# UNIT_V3_LVDS_Board.net
KiCad netlist of a schematic drawn in Altium Designer
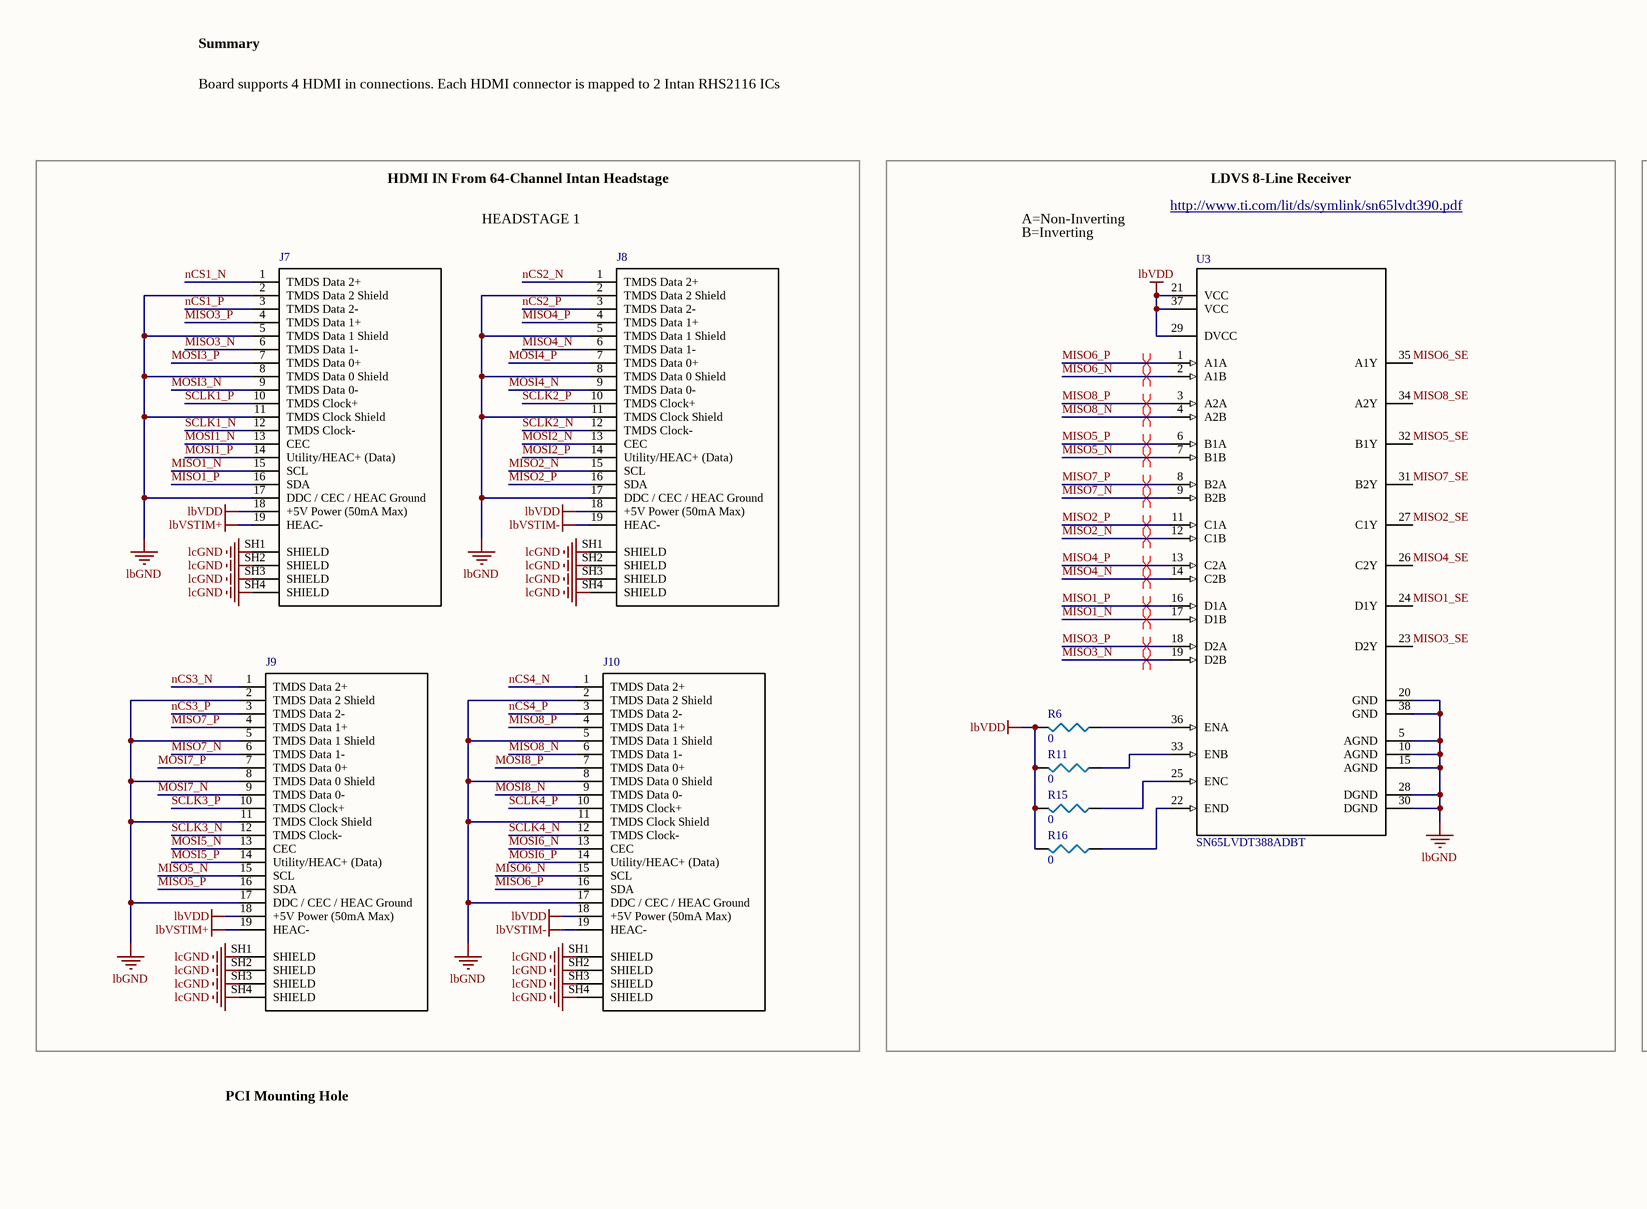
[diagram p0: UNIT_V3_LVDS_Board.SchDoc, left]
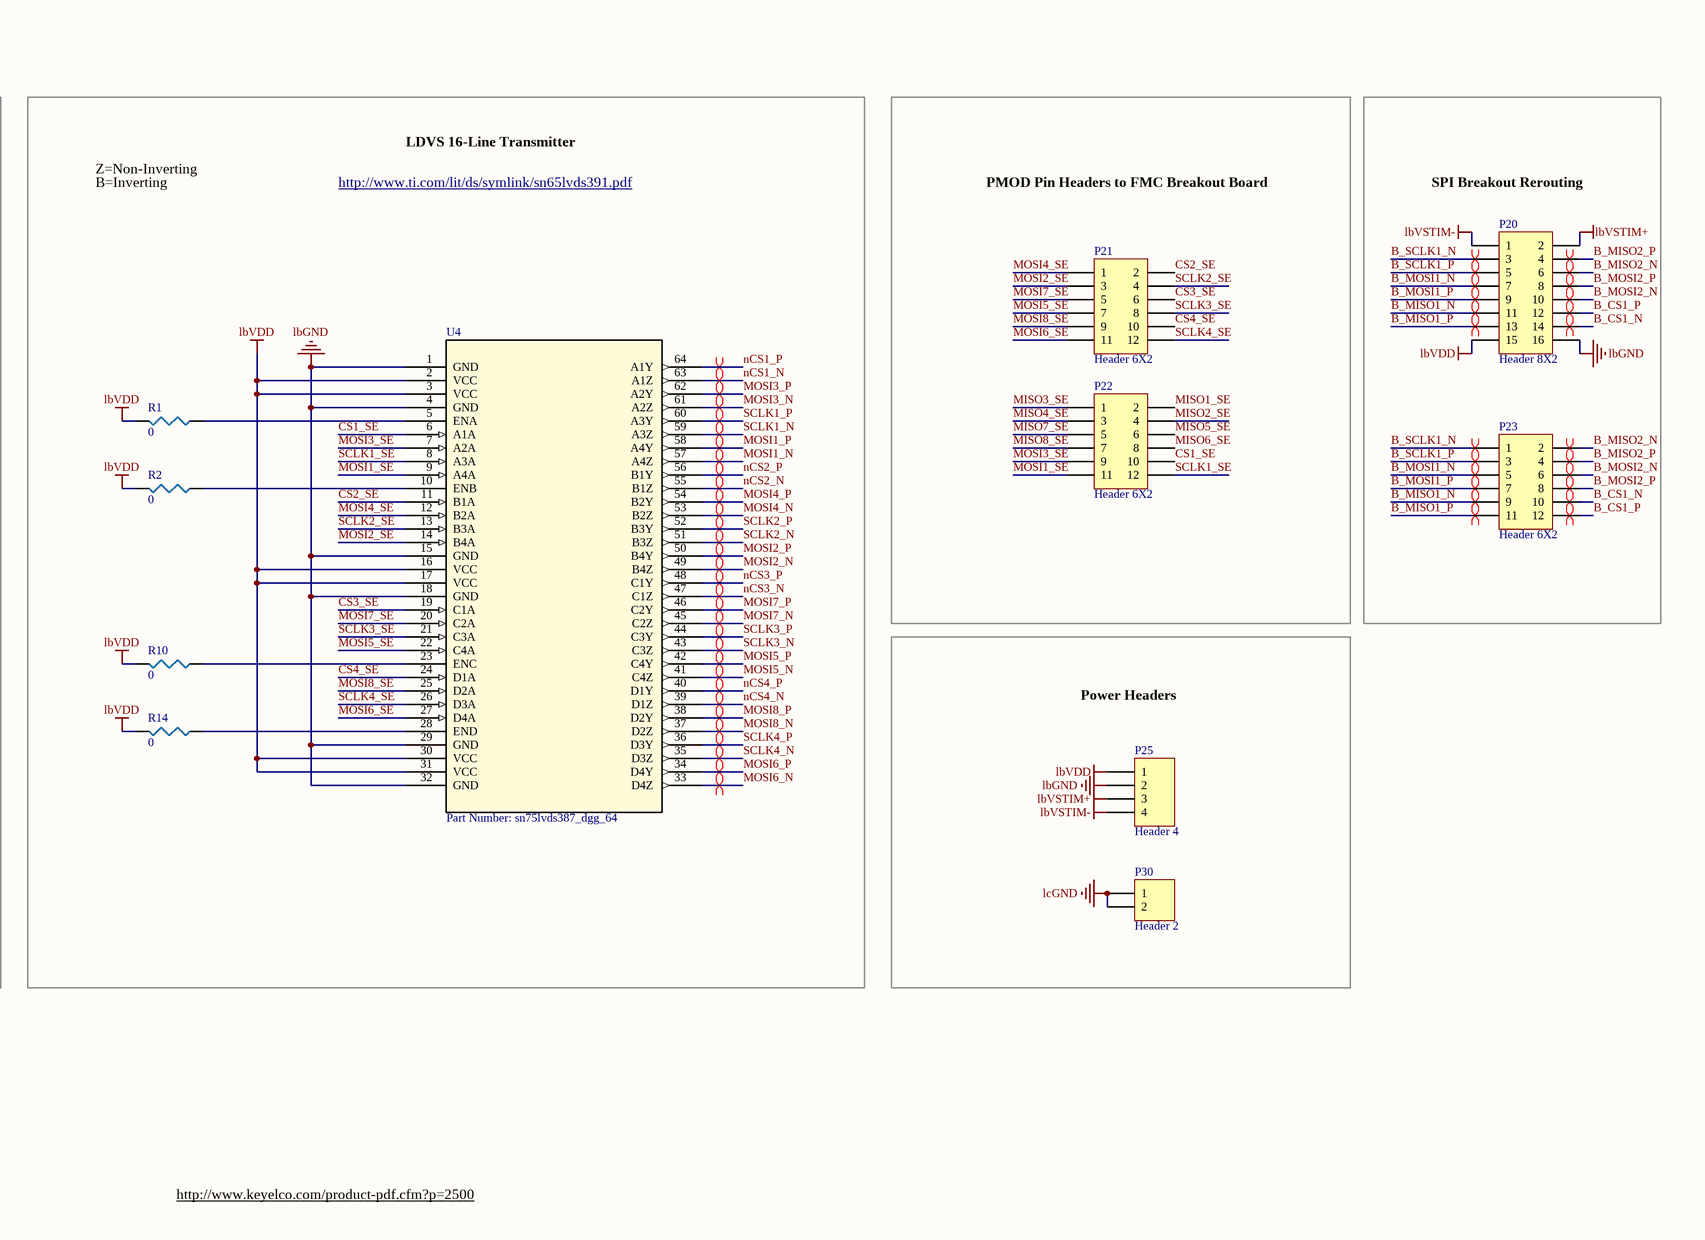
[diagram p1: UNIT_V3_LVDS_Board.SchDoc, right]

(export (version "E")
  (design (tool "Eeschema 10.0.6"))
  (components
    (comp (ref "J7")
      (value "1747981-2")
      (footprint "te_connectivity_audio_video_connectors:TE_1747981-2_1747981-2(Primary)")
      (description "Conn HDMI RCP 19 POS 0.5mm Solder ST SMD 19 Terminal 1 Port T/R")
      (fields (field (name "MF") "TE Connectivity"))
      (libsource (lib "te_connectivity_audio_video_connectors") (part "1747981-2"))
    )
    (comp (ref "J8")
      (value "1747981-2")
      (footprint "te_connectivity_audio_video_connectors:TE_1747981-2_1747981-2(Primary)")
      (description "Conn HDMI RCP 19 POS 0.5mm Solder ST SMD 19 Terminal 1 Port T/R")
      (fields (field (name "MF") "TE Connectivity"))
      (libsource (lib "te_connectivity_audio_video_connectors") (part "1747981-2"))
    )
    (comp (ref "J9")
      (value "1747981-2")
      (footprint "te_connectivity_audio_video_connectors:TE_1747981-2_1747981-2(Primary)")
      (description "Conn HDMI RCP 19 POS 0.5mm Solder ST SMD 19 Terminal 1 Port T/R")
      (fields (field (name "MF") "TE Connectivity"))
      (libsource (lib "te_connectivity_audio_video_connectors") (part "1747981-2"))
    )
    (comp (ref "J10")
      (value "1747981-2")
      (footprint "te_connectivity_audio_video_connectors:TE_1747981-2_1747981-2(Primary)")
      (description "Conn HDMI RCP 19 POS 0.5mm Solder ST SMD 19 Terminal 1 Port T/R")
      (fields (field (name "MF") "TE Connectivity"))
      (libsource (lib "te_connectivity_audio_video_connectors") (part "1747981-2"))
    )
    (comp (ref "P20")
      (value "Header 8X2")
      (footprint "te_connectivity_headers:TE_534998-8")
      (description "Header, 8-Pin, Dual row")
      (fields
        (field (name "MANUFACTURER") "TE Connectivity")
        (field (name "MANUFACTURER PART NUMBER") "534998-8")
        (field (name "PUBLISHER") "Altium Limited")
      )
      (libsource (lib "Miscellaneous Connectors") (part "Header 8X2"))
    )
    (comp (ref "P21")
      (value "Header 6X2")
      (footprint "molex_pcb_headers:0010897120")
      (description "Header, 6-Pin, Dual row")
      (fields (field (name "MANUFACTURER") "Molex") (field (name "MANUFACTURER PART NUMBER") "0010897120"))
      (libsource (lib "Miscellaneous Connectors") (part "Header 6X2"))
    )
    (comp (ref "P22")
      (value "Header 6X2")
      (footprint "molex_pcb_headers:0010897120")
      (description "Header, 6-Pin, Dual row")
      (fields
        (field (name "MANUFACTURER") "Molex")
        (field (name "MANUFACTURER PART NUMBER") "0010897120")
        (field (name "PUBLISHER") "Altium Limited")
      )
      (libsource (lib "Miscellaneous Connectors") (part "Header 6X2"))
    )
    (comp (ref "P23")
      (value "Header 6X2")
      (footprint "molex_pcb_headers:0010897120")
      (description "Header, 6-Pin, Dual row")
      (fields
        (field (name "MANUFACTURER") "Molex")
        (field (name "MANUFACTURER PART NUMBER") "0010897120")
        (field (name "PUBLISHER") "Altium Limited")
      )
      (libsource (lib "Miscellaneous Connectors") (part "Header 6X2"))
    )
    (comp (ref "P25")
      (value "Header 4")
      (footprint "on_shore_rising_clamp:OSTVN04A150")
      (description "Header, 4-Pin")
      (fields
        (field (name "MANUFACTURER") "On Shore Technology Inc.")
        (field (name "MANUFACTURER PART NUMBER") "OSTVN04A150")
        (field (name "PUBLISHER") "Altium Limited")
      )
      (libsource (lib "standard_components") (part "Header 4"))
    )
    (comp (ref "P30")
      (value "Header 2")
      (footprint "on_shore_rising_clamp:OSTVN02A150")
      (description "Header, 2-Pin")
      (fields
        (field (name "MANUFACTURER") "On Shore Technology Inc.")
        (field (name "MANUFACTURER PART NUMBER") "OSTVN02A150")
        (field (name "PUBLISHER") "Altium Limited")
      )
      (libsource (lib "Miscellaneous Connectors") (part "Header 2"))
    )
    (comp (ref "R1")
      (value "0")
      (footprint "standard_components:R0805")
      (description "RC0805JR-070RL")
      (fields (field (name "MANUFACTURER") "Yageo") (field (name "TOLERANCE") "1%"))
      (libsource (lib "standard_components") (part "RES0"))
    )
    (comp (ref "R2")
      (value "0")
      (footprint "standard_components:R0805")
      (description "RC0805JR-070RL")
      (fields (field (name "MANUFACTURER") "Yageo") (field (name "TOLERANCE") "1%"))
      (libsource (lib "standard_components") (part "RES0"))
    )
    (comp (ref "R6")
      (value "0")
      (footprint "standard_components:R0805")
      (description "RC0805JR-070RL")
      (fields (field (name "MANUFACTURER") "Yageo") (field (name "TOLERANCE") "1%"))
      (libsource (lib "standard_components") (part "RES0"))
    )
    (comp (ref "R10")
      (value "0")
      (footprint "standard_components:R0805")
      (description "RC0805JR-070RL")
      (fields (field (name "MANUFACTURER") "Yageo") (field (name "TOLERANCE") "1%"))
      (libsource (lib "standard_components") (part "RES0"))
    )
    (comp (ref "R11")
      (value "0")
      (footprint "standard_components:R0805")
      (description "RC0805JR-070RL")
      (fields (field (name "MANUFACTURER") "Yageo") (field (name "TOLERANCE") "1%"))
      (libsource (lib "standard_components") (part "RES0"))
    )
    (comp (ref "R14")
      (value "0")
      (footprint "standard_components:R0805")
      (description "RC0805JR-070RL")
      (fields (field (name "MANUFACTURER") "Yageo") (field (name "TOLERANCE") "1%"))
      (libsource (lib "standard_components") (part "RES0"))
    )
    (comp (ref "R15")
      (value "0")
      (footprint "standard_components:R0805")
      (description "RC0805JR-070RL")
      (fields (field (name "MANUFACTURER") "Yageo") (field (name "TOLERANCE") "1%"))
      (libsource (lib "standard_components") (part "RES0"))
    )
    (comp (ref "R16")
      (value "0")
      (footprint "standard_components:R0805")
      (description "RC0805JR-070RL")
      (fields (field (name "MANUFACTURER") "Yageo") (field (name "TOLERANCE") "1%"))
      (libsource (lib "standard_components") (part "RES0"))
    )
    (comp (ref "U3")
      (value "SN65LVDT388ADBT")
      (footprint "DBT0038A_N")
      (description "IC OCTAL LVDS RECEIVER 38-TSSOP")
      (fields
        (field (name "MANUFACTURER") "Texas Instruments")
        (field (name "PARTNUMBER") "SN65LVDT388ADBTR")
        (field (name "COPYRIGHT") "Copyright (C) 2018 Accelerated Designs. All rights reserved")
      )
      (libsource (lib "texas_insturments_interface_LVDS") (part "SN65LVDT388ADBTR"))
    )
    (comp (ref "U4")
      (value "Part Number: sn75lvds387_dgg_64")
      (footprint "texas_insturments_interface_LVDS:DGG64")
      (description "16-Channel LVDS Transmitter")
      (fields
        (field (name "MANUFACTURER") "Texas Instruments")
        (field (name "GENERIC_PART_NUMBER") "SN75LVDS387")
        (field (name "COPYRIGHT") "Copyright (C) 2018 Accelerated Designs. All rights reserved")
      )
      (libsource (lib "texas_insturments_interface_LVDS") (part "SN75LVDS387_DGG_64"))
    )
  )
  (nets
    (net (code "1") (name "/B_CS1_N") (class "Default")
      (node (ref "P20") (pin "14") (pinfunction "14_14") (pintype "passive"))
      (node (ref "P23") (pin "10") (pinfunction "10_10") (pintype "passive"))
    )
    (net (code "2") (name "/B_CS1_P") (class "Default")
      (node (ref "P20") (pin "12") (pinfunction "12_12") (pintype "passive"))
      (node (ref "P23") (pin "12") (pinfunction "12_12") (pintype "passive"))
    )
    (net (code "3") (name "/B_MISO1_N") (class "Default")
      (node (ref "P20") (pin "11") (pinfunction "11_11") (pintype "passive"))
      (node (ref "P23") (pin "9") (pinfunction "9_9") (pintype "passive"))
    )
    (net (code "4") (name "/B_MISO1_P") (class "Default")
      (node (ref "P20") (pin "13") (pinfunction "13_13") (pintype "passive"))
      (node (ref "P23") (pin "11") (pinfunction "11_11") (pintype "passive"))
    )
    (net (code "5") (name "/B_MISO2_N") (class "Default")
      (node (ref "P20") (pin "6") (pinfunction "6_6") (pintype "passive"))
      (node (ref "P23") (pin "2") (pinfunction "2_2") (pintype "passive"))
    )
    (net (code "6") (name "/B_MISO2_P") (class "Default")
      (node (ref "P20") (pin "4") (pinfunction "4_4") (pintype "passive"))
      (node (ref "P23") (pin "4") (pinfunction "4_4") (pintype "passive"))
    )
    (net (code "7") (name "/B_MOSI1_N") (class "Default")
      (node (ref "P20") (pin "7") (pinfunction "7_7") (pintype "passive"))
      (node (ref "P23") (pin "5") (pinfunction "5_5") (pintype "passive"))
    )
    (net (code "8") (name "/B_MOSI1_P") (class "Default")
      (node (ref "P20") (pin "9") (pinfunction "9_9") (pintype "passive"))
      (node (ref "P23") (pin "7") (pinfunction "7_7") (pintype "passive"))
    )
    (net (code "9") (name "/B_MOSI2_N") (class "Default")
      (node (ref "P20") (pin "10") (pinfunction "10_10") (pintype "passive"))
      (node (ref "P23") (pin "6") (pinfunction "6_6") (pintype "passive"))
    )
    (net (code "10") (name "/B_MOSI2_P") (class "Default")
      (node (ref "P20") (pin "8") (pinfunction "8_8") (pintype "passive"))
      (node (ref "P23") (pin "8") (pinfunction "8_8") (pintype "passive"))
    )
    (net (code "11") (name "/B_SCLK1_N") (class "Default")
      (node (ref "P20") (pin "3") (pinfunction "3_3") (pintype "passive"))
      (node (ref "P23") (pin "1") (pinfunction "1_1") (pintype "passive"))
    )
    (net (code "12") (name "/B_SCLK1_P") (class "Default")
      (node (ref "P20") (pin "5") (pinfunction "5_5") (pintype "passive"))
      (node (ref "P23") (pin "3") (pinfunction "3_3") (pintype "passive"))
    )
    (net (code "13") (name "/CS1_SE") (class "Default")
      (node (ref "P22") (pin "10") (pinfunction "10_10") (pintype "passive"))
      (node (ref "U4") (pin "6") (pinfunction "A1A_6") (pintype "input"))
    )
    (net (code "14") (name "/CS2_SE") (class "Default")
      (node (ref "P21") (pin "2") (pinfunction "2_2") (pintype "passive"))
      (node (ref "U4") (pin "11") (pinfunction "B1A_11") (pintype "input"))
    )
    (net (code "15") (name "/CS3_SE") (class "Default")
      (node (ref "P21") (pin "6") (pinfunction "6_6") (pintype "passive"))
      (node (ref "U4") (pin "19") (pinfunction "C1A_19") (pintype "input"))
    )
    (net (code "16") (name "/CS4_SE") (class "Default")
      (node (ref "P21") (pin "10") (pinfunction "10_10") (pintype "passive"))
      (node (ref "U4") (pin "24") (pinfunction "D1A_24") (pintype "input"))
    )
    (net (code "17") (name "/MISO1_N") (class "Default")
      (node (ref "J7") (pin "15") (pinfunction "SCL_15") (pintype "passive"))
      (node (ref "U3") (pin "17") (pinfunction "D1B_17") (pintype "input"))
    )
    (net (code "18") (name "/MISO1_P") (class "Default")
      (node (ref "J7") (pin "16") (pinfunction "SDA_16") (pintype "passive"))
      (node (ref "U3") (pin "16") (pinfunction "D1A_16") (pintype "input"))
    )
    (net (code "19") (name "/MISO1_SE") (class "Default")
      (node (ref "P22") (pin "2") (pinfunction "2_2") (pintype "passive"))
      (node (ref "U3") (pin "24") (pinfunction "D1Y_24") (pintype "tri_state"))
    )
    (net (code "20") (name "/MISO2_N") (class "Default")
      (node (ref "J8") (pin "15") (pinfunction "SCL_15") (pintype "passive"))
      (node (ref "U3") (pin "12") (pinfunction "C1B_12") (pintype "input"))
    )
    (net (code "21") (name "/MISO2_P") (class "Default")
      (node (ref "J8") (pin "16") (pinfunction "SDA_16") (pintype "passive"))
      (node (ref "U3") (pin "11") (pinfunction "C1A_11") (pintype "input"))
    )
    (net (code "22") (name "/MISO2_SE") (class "Default")
      (node (ref "P22") (pin "4") (pinfunction "4_4") (pintype "passive"))
      (node (ref "U3") (pin "27") (pinfunction "C1Y_27") (pintype "tri_state"))
    )
    (net (code "23") (name "/MISO3_N") (class "Default")
      (node (ref "J7") (pin "6") (pinfunction "TMDS_Data_1-_6") (pintype "passive"))
      (node (ref "U3") (pin "19") (pinfunction "D2B_19") (pintype "input"))
    )
    (net (code "24") (name "/MISO3_P") (class "Default")
      (node (ref "J7") (pin "4") (pinfunction "TMDS_Data_1+_4") (pintype "passive"))
      (node (ref "U3") (pin "18") (pinfunction "D2A_18") (pintype "input"))
    )
    (net (code "25") (name "/MISO3_SE") (class "Default")
      (node (ref "P22") (pin "1") (pinfunction "1_1") (pintype "passive"))
      (node (ref "U3") (pin "23") (pinfunction "D2Y_23") (pintype "tri_state"))
    )
    (net (code "26") (name "/MISO4_N") (class "Default")
      (node (ref "J8") (pin "6") (pinfunction "TMDS_Data_1-_6") (pintype "passive"))
      (node (ref "U3") (pin "14") (pinfunction "C2B_14") (pintype "input"))
    )
    (net (code "27") (name "/MISO4_P") (class "Default")
      (node (ref "J8") (pin "4") (pinfunction "TMDS_Data_1+_4") (pintype "passive"))
      (node (ref "U3") (pin "13") (pinfunction "C2A_13") (pintype "input"))
    )
    (net (code "28") (name "/MISO4_SE") (class "Default")
      (node (ref "P22") (pin "3") (pinfunction "3_3") (pintype "passive"))
      (node (ref "U3") (pin "26") (pinfunction "C2Y_26") (pintype "tri_state"))
    )
    (net (code "29") (name "/MISO5_N") (class "Default")
      (node (ref "J9") (pin "15") (pinfunction "SCL_15") (pintype "passive"))
      (node (ref "U3") (pin "7") (pinfunction "B1B_7") (pintype "input"))
    )
    (net (code "30") (name "/MISO5_P") (class "Default")
      (node (ref "J9") (pin "16") (pinfunction "SDA_16") (pintype "passive"))
      (node (ref "U3") (pin "6") (pinfunction "B1A_6") (pintype "input"))
    )
    (net (code "31") (name "/MISO5_SE") (class "Default")
      (node (ref "P22") (pin "6") (pinfunction "6_6") (pintype "passive"))
      (node (ref "U3") (pin "32") (pinfunction "B1Y_32") (pintype "tri_state"))
    )
    (net (code "32") (name "/MISO6_N") (class "Default")
      (node (ref "J10") (pin "15") (pinfunction "SCL_15") (pintype "passive"))
      (node (ref "U3") (pin "2") (pinfunction "A1B_2") (pintype "input"))
    )
    (net (code "33") (name "/MISO6_P") (class "Default")
      (node (ref "J10") (pin "16") (pinfunction "SDA_16") (pintype "passive"))
      (node (ref "U3") (pin "1") (pinfunction "A1A_1") (pintype "input"))
    )
    (net (code "34") (name "/MISO6_SE") (class "Default")
      (node (ref "P22") (pin "8") (pinfunction "8_8") (pintype "passive"))
      (node (ref "U3") (pin "35") (pinfunction "A1Y_35") (pintype "tri_state"))
    )
    (net (code "35") (name "/MISO7_N") (class "Default")
      (node (ref "J9") (pin "6") (pinfunction "TMDS_Data_1-_6") (pintype "passive"))
      (node (ref "U3") (pin "9") (pinfunction "B2B_9") (pintype "input"))
    )
    (net (code "36") (name "/MISO7_P") (class "Default")
      (node (ref "J9") (pin "4") (pinfunction "TMDS_Data_1+_4") (pintype "passive"))
      (node (ref "U3") (pin "8") (pinfunction "B2A_8") (pintype "input"))
    )
    (net (code "37") (name "/MISO7_SE") (class "Default")
      (node (ref "P22") (pin "5") (pinfunction "5_5") (pintype "passive"))
      (node (ref "U3") (pin "31") (pinfunction "B2Y_31") (pintype "tri_state"))
    )
    (net (code "38") (name "/MISO8_N") (class "Default")
      (node (ref "J10") (pin "6") (pinfunction "TMDS_Data_1-_6") (pintype "passive"))
      (node (ref "U3") (pin "4") (pinfunction "A2B_4") (pintype "input"))
    )
    (net (code "39") (name "/MISO8_P") (class "Default")
      (node (ref "J10") (pin "4") (pinfunction "TMDS_Data_1+_4") (pintype "passive"))
      (node (ref "U3") (pin "3") (pinfunction "A2A_3") (pintype "input"))
    )
    (net (code "40") (name "/MISO8_SE") (class "Default")
      (node (ref "P22") (pin "7") (pinfunction "7_7") (pintype "passive"))
      (node (ref "U3") (pin "34") (pinfunction "A2Y_34") (pintype "tri_state"))
    )
    (net (code "41") (name "/MOSI1_N") (class "Default")
      (node (ref "J7") (pin "13") (pinfunction "CEC_13") (pintype "passive"))
      (node (ref "U4") (pin "57") (pinfunction "A4Z_57") (pintype "output"))
    )
    (net (code "42") (name "/MOSI1_P") (class "Default")
      (node (ref "J7") (pin "14") (pinfunction "Utility/HEAC+_(Data)_14") (pintype "passive"))
      (node (ref "U4") (pin "58") (pinfunction "A4Y_58") (pintype "output"))
    )
    (net (code "43") (name "/MOSI1_SE") (class "Default")
      (node (ref "P22") (pin "11") (pinfunction "11_11") (pintype "passive"))
      (node (ref "U4") (pin "9") (pinfunction "A4A_9") (pintype "input"))
    )
    (net (code "44") (name "/MOSI2_N") (class "Default")
      (node (ref "J8") (pin "13") (pinfunction "CEC_13") (pintype "passive"))
      (node (ref "U4") (pin "49") (pinfunction "B4Z_49") (pintype "output"))
    )
    (net (code "45") (name "/MOSI2_P") (class "Default")
      (node (ref "J8") (pin "14") (pinfunction "Utility/HEAC+_(Data)_14") (pintype "passive"))
      (node (ref "U4") (pin "50") (pinfunction "B4Y_50") (pintype "output"))
    )
    (net (code "46") (name "/MOSI2_SE") (class "Default")
      (node (ref "P21") (pin "3") (pinfunction "3_3") (pintype "passive"))
      (node (ref "U4") (pin "14") (pinfunction "B4A_14") (pintype "input"))
    )
    (net (code "47") (name "/MOSI3_N") (class "Default")
      (node (ref "J7") (pin "9") (pinfunction "TMDS_Data_0-_9") (pintype "passive"))
      (node (ref "U4") (pin "61") (pinfunction "A2Z_61") (pintype "output"))
    )
    (net (code "48") (name "/MOSI3_P") (class "Default")
      (node (ref "J7") (pin "7") (pinfunction "TMDS_Data_0+_7") (pintype "passive"))
      (node (ref "U4") (pin "62") (pinfunction "A2Y_62") (pintype "output"))
    )
    (net (code "49") (name "/MOSI3_SE") (class "Default")
      (node (ref "P22") (pin "9") (pinfunction "9_9") (pintype "passive"))
      (node (ref "U4") (pin "7") (pinfunction "A2A_7") (pintype "input"))
    )
    (net (code "50") (name "/MOSI4_N") (class "Default")
      (node (ref "J8") (pin "9") (pinfunction "TMDS_Data_0-_9") (pintype "passive"))
      (node (ref "U4") (pin "53") (pinfunction "B2Z_53") (pintype "output"))
    )
    (net (code "51") (name "/MOSI4_P") (class "Default")
      (node (ref "J8") (pin "7") (pinfunction "TMDS_Data_0+_7") (pintype "passive"))
      (node (ref "U4") (pin "54") (pinfunction "B2Y_54") (pintype "output"))
    )
    (net (code "52") (name "/MOSI4_SE") (class "Default")
      (node (ref "P21") (pin "1") (pinfunction "1_1") (pintype "passive"))
      (node (ref "U4") (pin "12") (pinfunction "B2A_12") (pintype "input"))
    )
    (net (code "53") (name "/MOSI5_N") (class "Default")
      (node (ref "J9") (pin "13") (pinfunction "CEC_13") (pintype "passive"))
      (node (ref "U4") (pin "41") (pinfunction "C4Z_41") (pintype "output"))
    )
    (net (code "54") (name "/MOSI5_P") (class "Default")
      (node (ref "J9") (pin "14") (pinfunction "Utility/HEAC+_(Data)_14") (pintype "passive"))
      (node (ref "U4") (pin "42") (pinfunction "C4Y_42") (pintype "output"))
    )
    (net (code "55") (name "/MOSI5_SE") (class "Default")
      (node (ref "P21") (pin "7") (pinfunction "7_7") (pintype "passive"))
      (node (ref "U4") (pin "22") (pinfunction "C4A_22") (pintype "input"))
    )
    (net (code "56") (name "/MOSI6_N") (class "Default")
      (node (ref "J10") (pin "13") (pinfunction "CEC_13") (pintype "passive"))
      (node (ref "U4") (pin "33") (pinfunction "D4Z_33") (pintype "output"))
    )
    (net (code "57") (name "/MOSI6_P") (class "Default")
      (node (ref "J10") (pin "14") (pinfunction "Utility/HEAC+_(Data)_14") (pintype "passive"))
      (node (ref "U4") (pin "34") (pinfunction "D4Y_34") (pintype "output"))
    )
    (net (code "58") (name "/MOSI6_SE") (class "Default")
      (node (ref "P21") (pin "11") (pinfunction "11_11") (pintype "passive"))
      (node (ref "U4") (pin "27") (pinfunction "D4A_27") (pintype "input"))
    )
    (net (code "59") (name "/MOSI7_N") (class "Default")
      (node (ref "J9") (pin "9") (pinfunction "TMDS_Data_0-_9") (pintype "passive"))
      (node (ref "U4") (pin "45") (pinfunction "C2Z_45") (pintype "output"))
    )
    (net (code "60") (name "/MOSI7_P") (class "Default")
      (node (ref "J9") (pin "7") (pinfunction "TMDS_Data_0+_7") (pintype "passive"))
      (node (ref "U4") (pin "46") (pinfunction "C2Y_46") (pintype "output"))
    )
    (net (code "61") (name "/MOSI7_SE") (class "Default")
      (node (ref "P21") (pin "5") (pinfunction "5_5") (pintype "passive"))
      (node (ref "U4") (pin "20") (pinfunction "C2A_20") (pintype "input"))
    )
    (net (code "62") (name "/MOSI8_N") (class "Default")
      (node (ref "J10") (pin "9") (pinfunction "TMDS_Data_0-_9") (pintype "passive"))
      (node (ref "U4") (pin "37") (pinfunction "D2Z_37") (pintype "output"))
    )
    (net (code "63") (name "/MOSI8_P") (class "Default")
      (node (ref "J10") (pin "7") (pinfunction "TMDS_Data_0+_7") (pintype "passive"))
      (node (ref "U4") (pin "38") (pinfunction "D2Y_38") (pintype "output"))
    )
    (net (code "64") (name "/MOSI8_SE") (class "Default")
      (node (ref "P21") (pin "9") (pinfunction "9_9") (pintype "passive"))
      (node (ref "U4") (pin "25") (pinfunction "D2A_25") (pintype "input"))
    )
    (net (code "65") (name "/SCLK1_N") (class "Default")
      (node (ref "J7") (pin "12") (pinfunction "TMDS_Clock-_12") (pintype "passive"))
      (node (ref "U4") (pin "59") (pinfunction "A3Z_59") (pintype "output"))
    )
    (net (code "66") (name "/SCLK1_P") (class "Default")
      (node (ref "J7") (pin "10") (pinfunction "TMDS_Clock+_10") (pintype "passive"))
      (node (ref "U4") (pin "60") (pinfunction "A3Y_60") (pintype "output"))
    )
    (net (code "67") (name "/SCLK1_SE") (class "Default")
      (node (ref "P22") (pin "12") (pinfunction "12_12") (pintype "passive"))
      (node (ref "U4") (pin "8") (pinfunction "A3A_8") (pintype "input"))
    )
    (net (code "68") (name "/SCLK2_N") (class "Default")
      (node (ref "J8") (pin "12") (pinfunction "TMDS_Clock-_12") (pintype "passive"))
      (node (ref "U4") (pin "51") (pinfunction "B3Z_51") (pintype "output"))
    )
    (net (code "69") (name "/SCLK2_P") (class "Default")
      (node (ref "J8") (pin "10") (pinfunction "TMDS_Clock+_10") (pintype "passive"))
      (node (ref "U4") (pin "52") (pinfunction "B3Y_52") (pintype "output"))
    )
    (net (code "70") (name "/SCLK2_SE") (class "Default")
      (node (ref "P21") (pin "4") (pinfunction "4_4") (pintype "passive"))
      (node (ref "U4") (pin "13") (pinfunction "B3A_13") (pintype "input"))
    )
    (net (code "71") (name "/SCLK3_N") (class "Default")
      (node (ref "J9") (pin "12") (pinfunction "TMDS_Clock-_12") (pintype "passive"))
      (node (ref "U4") (pin "43") (pinfunction "C3Z_43") (pintype "output"))
    )
    (net (code "72") (name "/SCLK3_P") (class "Default")
      (node (ref "J9") (pin "10") (pinfunction "TMDS_Clock+_10") (pintype "passive"))
      (node (ref "U4") (pin "44") (pinfunction "C3Y_44") (pintype "output"))
    )
    (net (code "73") (name "/SCLK3_SE") (class "Default")
      (node (ref "P21") (pin "8") (pinfunction "8_8") (pintype "passive"))
      (node (ref "U4") (pin "21") (pinfunction "C3A_21") (pintype "input"))
    )
    (net (code "74") (name "/SCLK4_N") (class "Default")
      (node (ref "J10") (pin "12") (pinfunction "TMDS_Clock-_12") (pintype "passive"))
      (node (ref "U4") (pin "35") (pinfunction "D3Z_35") (pintype "output"))
    )
    (net (code "75") (name "/SCLK4_P") (class "Default")
      (node (ref "J10") (pin "10") (pinfunction "TMDS_Clock+_10") (pintype "passive"))
      (node (ref "U4") (pin "36") (pinfunction "D3Y_36") (pintype "output"))
    )
    (net (code "76") (name "/SCLK4_SE") (class "Default")
      (node (ref "P21") (pin "12") (pinfunction "12_12") (pintype "passive"))
      (node (ref "U4") (pin "26") (pinfunction "D3A_26") (pintype "input"))
    )
    (net (code "77") (name "/nCS1_N") (class "Default")
      (node (ref "J7") (pin "1") (pinfunction "TMDS_Data_2+_1") (pintype "passive"))
      (node (ref "U4") (pin "63") (pinfunction "A1Z_63") (pintype "output"))
    )
    (net (code "78") (name "/nCS1_P") (class "Default")
      (node (ref "J7") (pin "3") (pinfunction "TMDS_Data_2-_3") (pintype "passive"))
      (node (ref "U4") (pin "64") (pinfunction "A1Y_64") (pintype "output"))
    )
    (net (code "79") (name "/nCS2_N") (class "Default")
      (node (ref "J8") (pin "1") (pinfunction "TMDS_Data_2+_1") (pintype "passive"))
      (node (ref "U4") (pin "55") (pinfunction "B1Z_55") (pintype "output"))
    )
    (net (code "80") (name "/nCS2_P") (class "Default")
      (node (ref "J8") (pin "3") (pinfunction "TMDS_Data_2-_3") (pintype "passive"))
      (node (ref "U4") (pin "56") (pinfunction "B1Y_56") (pintype "output"))
    )
    (net (code "81") (name "/nCS3_N") (class "Default")
      (node (ref "J9") (pin "1") (pinfunction "TMDS_Data_2+_1") (pintype "passive"))
      (node (ref "U4") (pin "47") (pinfunction "C1Z_47") (pintype "output"))
    )
    (net (code "82") (name "/nCS3_P") (class "Default")
      (node (ref "J9") (pin "3") (pinfunction "TMDS_Data_2-_3") (pintype "passive"))
      (node (ref "U4") (pin "48") (pinfunction "C1Y_48") (pintype "output"))
    )
    (net (code "83") (name "/nCS4_N") (class "Default")
      (node (ref "J10") (pin "1") (pinfunction "TMDS_Data_2+_1") (pintype "passive"))
      (node (ref "U4") (pin "39") (pinfunction "D1Z_39") (pintype "output"))
    )
    (net (code "84") (name "/nCS4_P") (class "Default")
      (node (ref "J10") (pin "3") (pinfunction "TMDS_Data_2-_3") (pintype "passive"))
      (node (ref "U4") (pin "40") (pinfunction "D1Y_40") (pintype "output"))
    )
    (net (code "85") (name "Net-(U3-ENA)") (class "Default")
      (node (ref "R6") (pin "1") (pinfunction "1_1") (pintype "passive"))
      (node (ref "U3") (pin "36") (pinfunction "ENA_36") (pintype "input"))
    )
    (net (code "86") (name "Net-(U3-ENB)") (class "Default")
      (node (ref "R11") (pin "1") (pinfunction "1_1") (pintype "passive"))
      (node (ref "U3") (pin "33") (pinfunction "ENB_33") (pintype "input"))
    )
    (net (code "87") (name "Net-(U3-ENC)") (class "Default")
      (node (ref "R15") (pin "1") (pinfunction "1_1") (pintype "passive"))
      (node (ref "U3") (pin "25") (pinfunction "ENC_25") (pintype "input"))
    )
    (net (code "88") (name "Net-(U3-END)") (class "Default")
      (node (ref "R16") (pin "1") (pinfunction "1_1") (pintype "passive"))
      (node (ref "U3") (pin "22") (pinfunction "END_22") (pintype "input"))
    )
    (net (code "89") (name "Net-(U4-ENA)") (class "Default")
      (node (ref "R1") (pin "1") (pinfunction "1_1") (pintype "passive"))
      (node (ref "U4") (pin "5") (pinfunction "ENA_5") (pintype "passive"))
    )
    (net (code "90") (name "Net-(U4-ENB)") (class "Default")
      (node (ref "R2") (pin "1") (pinfunction "1_1") (pintype "passive"))
      (node (ref "U4") (pin "10") (pinfunction "ENB_10") (pintype "passive"))
    )
    (net (code "91") (name "Net-(U4-ENC)") (class "Default")
      (node (ref "R10") (pin "1") (pinfunction "1_1") (pintype "passive"))
      (node (ref "U4") (pin "23") (pinfunction "ENC_23") (pintype "passive"))
    )
    (net (code "92") (name "Net-(U4-END)") (class "Default")
      (node (ref "R14") (pin "1") (pinfunction "1_1") (pintype "passive"))
      (node (ref "U4") (pin "28") (pinfunction "END_28") (pintype "passive"))
    )
    (net (code "93") (name "lbGND") (class "Default")
      (node (ref "J10") (pin "11") (pinfunction "TMDS_Clock_Shield_11") (pintype "passive"))
      (node (ref "J10") (pin "17") (pinfunction "DDC_/_CEC_/_HEAC_Ground_17") (pintype "passive"))
      (node (ref "J10") (pin "2") (pinfunction "TMDS_Data_2_Shield_2") (pintype "passive"))
      (node (ref "J10") (pin "5") (pinfunction "TMDS_Data_1_Shield_5") (pintype "passive"))
      (node (ref "J10") (pin "8") (pinfunction "TMDS_Data_0_Shield_8") (pintype "passive"))
      (node (ref "J7") (pin "11") (pinfunction "TMDS_Clock_Shield_11") (pintype "passive"))
      (node (ref "J7") (pin "17") (pinfunction "DDC_/_CEC_/_HEAC_Ground_17") (pintype "passive"))
      (node (ref "J7") (pin "2") (pinfunction "TMDS_Data_2_Shield_2") (pintype "passive"))
      (node (ref "J7") (pin "5") (pinfunction "TMDS_Data_1_Shield_5") (pintype "passive"))
      (node (ref "J7") (pin "8") (pinfunction "TMDS_Data_0_Shield_8") (pintype "passive"))
      (node (ref "J8") (pin "11") (pinfunction "TMDS_Clock_Shield_11") (pintype "passive"))
      (node (ref "J8") (pin "17") (pinfunction "DDC_/_CEC_/_HEAC_Ground_17") (pintype "passive"))
      (node (ref "J8") (pin "2") (pinfunction "TMDS_Data_2_Shield_2") (pintype "passive"))
      (node (ref "J8") (pin "5") (pinfunction "TMDS_Data_1_Shield_5") (pintype "passive"))
      (node (ref "J8") (pin "8") (pinfunction "TMDS_Data_0_Shield_8") (pintype "passive"))
      (node (ref "J9") (pin "11") (pinfunction "TMDS_Clock_Shield_11") (pintype "passive"))
      (node (ref "J9") (pin "17") (pinfunction "DDC_/_CEC_/_HEAC_Ground_17") (pintype "passive"))
      (node (ref "J9") (pin "2") (pinfunction "TMDS_Data_2_Shield_2") (pintype "passive"))
      (node (ref "J9") (pin "5") (pinfunction "TMDS_Data_1_Shield_5") (pintype "passive"))
      (node (ref "J9") (pin "8") (pinfunction "TMDS_Data_0_Shield_8") (pintype "passive"))
      (node (ref "P20") (pin "16") (pinfunction "16_16") (pintype "passive"))
      (node (ref "P25") (pin "2") (pinfunction "2_2") (pintype "passive"))
      (node (ref "U3") (pin "10") (pinfunction "AGND_10") (pintype "power_in"))
      (node (ref "U3") (pin "15") (pinfunction "AGND_15") (pintype "power_in"))
      (node (ref "U3") (pin "20") (pinfunction "GND_20") (pintype "power_in"))
      (node (ref "U3") (pin "28") (pinfunction "DGND_28") (pintype "power_in"))
      (node (ref "U3") (pin "30") (pinfunction "DGND_30") (pintype "power_in"))
      (node (ref "U3") (pin "38") (pinfunction "GND_38") (pintype "power_in"))
      (node (ref "U3") (pin "5") (pinfunction "AGND_5") (pintype "power_in"))
      (node (ref "U4") (pin "1") (pinfunction "GND_1") (pintype "power_in"))
      (node (ref "U4") (pin "15") (pinfunction "GND_15") (pintype "power_in"))
      (node (ref "U4") (pin "18") (pinfunction "GND_18") (pintype "power_in"))
      (node (ref "U4") (pin "29") (pinfunction "GND_29") (pintype "power_in"))
      (node (ref "U4") (pin "32") (pinfunction "GND_32") (pintype "power_in"))
      (node (ref "U4") (pin "4") (pinfunction "GND_4") (pintype "power_in"))
    )
    (net (code "94") (name "lbVDD") (class "Default")
      (node (ref "J10") (pin "18") (pinfunction "+5V_Power_(50mA_Max)_18") (pintype "passive"))
      (node (ref "J7") (pin "18") (pinfunction "+5V_Power_(50mA_Max)_18") (pintype "passive"))
      (node (ref "J8") (pin "18") (pinfunction "+5V_Power_(50mA_Max)_18") (pintype "passive"))
      (node (ref "J9") (pin "18") (pinfunction "+5V_Power_(50mA_Max)_18") (pintype "passive"))
      (node (ref "P20") (pin "15") (pinfunction "15_15") (pintype "passive"))
      (node (ref "P25") (pin "1") (pinfunction "1_1") (pintype "passive"))
      (node (ref "R1") (pin "2") (pinfunction "2_2") (pintype "passive"))
      (node (ref "R10") (pin "2") (pinfunction "2_2") (pintype "passive"))
      (node (ref "R11") (pin "2") (pinfunction "2_2") (pintype "passive"))
      (node (ref "R14") (pin "2") (pinfunction "2_2") (pintype "passive"))
      (node (ref "R15") (pin "2") (pinfunction "2_2") (pintype "passive"))
      (node (ref "R16") (pin "2") (pinfunction "2_2") (pintype "passive"))
      (node (ref "R2") (pin "2") (pinfunction "2_2") (pintype "passive"))
      (node (ref "R6") (pin "2") (pinfunction "2_2") (pintype "passive"))
      (node (ref "U3") (pin "21") (pinfunction "VCC_21") (pintype "power_in"))
      (node (ref "U3") (pin "29") (pinfunction "DVCC_29") (pintype "power_in"))
      (node (ref "U3") (pin "37") (pinfunction "VCC_37") (pintype "power_in"))
      (node (ref "U4") (pin "16") (pinfunction "VCC_16") (pintype "power_in"))
      (node (ref "U4") (pin "17") (pinfunction "VCC_17") (pintype "power_in"))
      (node (ref "U4") (pin "2") (pinfunction "VCC_2") (pintype "power_in"))
      (node (ref "U4") (pin "3") (pinfunction "VCC_3") (pintype "power_in"))
      (node (ref "U4") (pin "30") (pinfunction "VCC_30") (pintype "power_in"))
      (node (ref "U4") (pin "31") (pinfunction "VCC_31") (pintype "power_in"))
    )
    (net (code "95") (name "lbVSTIM+") (class "Default")
      (node (ref "J7") (pin "19") (pinfunction "HEAC-_19") (pintype "passive"))
      (node (ref "J9") (pin "19") (pinfunction "HEAC-_19") (pintype "passive"))
      (node (ref "P20") (pin "2") (pinfunction "2_2") (pintype "passive"))
      (node (ref "P25") (pin "3") (pinfunction "3_3") (pintype "passive"))
    )
    (net (code "96") (name "lbVSTIM-") (class "Default")
      (node (ref "J10") (pin "19") (pinfunction "HEAC-_19") (pintype "passive"))
      (node (ref "J8") (pin "19") (pinfunction "HEAC-_19") (pintype "passive"))
      (node (ref "P20") (pin "1") (pinfunction "1_1") (pintype "passive"))
      (node (ref "P25") (pin "4") (pinfunction "4_4") (pintype "passive"))
    )
    (net (code "97") (name "lcGND") (class "Default")
      (node (ref "J10") (pin "SH1") (pinfunction "SHIELD_SH1") (pintype "passive"))
      (node (ref "J10") (pin "SH2") (pinfunction "SHIELD_SH2") (pintype "passive"))
      (node (ref "J10") (pin "SH3") (pinfunction "SHIELD_SH3") (pintype "passive"))
      (node (ref "J10") (pin "SH4") (pinfunction "SHIELD_SH4") (pintype "passive"))
      (node (ref "J7") (pin "SH1") (pinfunction "SHIELD_SH1") (pintype "passive"))
      (node (ref "J7") (pin "SH2") (pinfunction "SHIELD_SH2") (pintype "passive"))
      (node (ref "J7") (pin "SH3") (pinfunction "SHIELD_SH3") (pintype "passive"))
      (node (ref "J7") (pin "SH4") (pinfunction "SHIELD_SH4") (pintype "passive"))
      (node (ref "J8") (pin "SH1") (pinfunction "SHIELD_SH1") (pintype "passive"))
      (node (ref "J8") (pin "SH2") (pinfunction "SHIELD_SH2") (pintype "passive"))
      (node (ref "J8") (pin "SH3") (pinfunction "SHIELD_SH3") (pintype "passive"))
      (node (ref "J8") (pin "SH4") (pinfunction "SHIELD_SH4") (pintype "passive"))
      (node (ref "J9") (pin "SH1") (pinfunction "SHIELD_SH1") (pintype "passive"))
      (node (ref "J9") (pin "SH2") (pinfunction "SHIELD_SH2") (pintype "passive"))
      (node (ref "J9") (pin "SH3") (pinfunction "SHIELD_SH3") (pintype "passive"))
      (node (ref "J9") (pin "SH4") (pinfunction "SHIELD_SH4") (pintype "passive"))
      (node (ref "P30") (pin "1") (pinfunction "1_1") (pintype "passive"))
      (node (ref "P30") (pin "2") (pinfunction "2_2") (pintype "passive"))
    )
  )
)
